# Connectors.net
KiCad netlist of a schematic drawn in Altium Designer
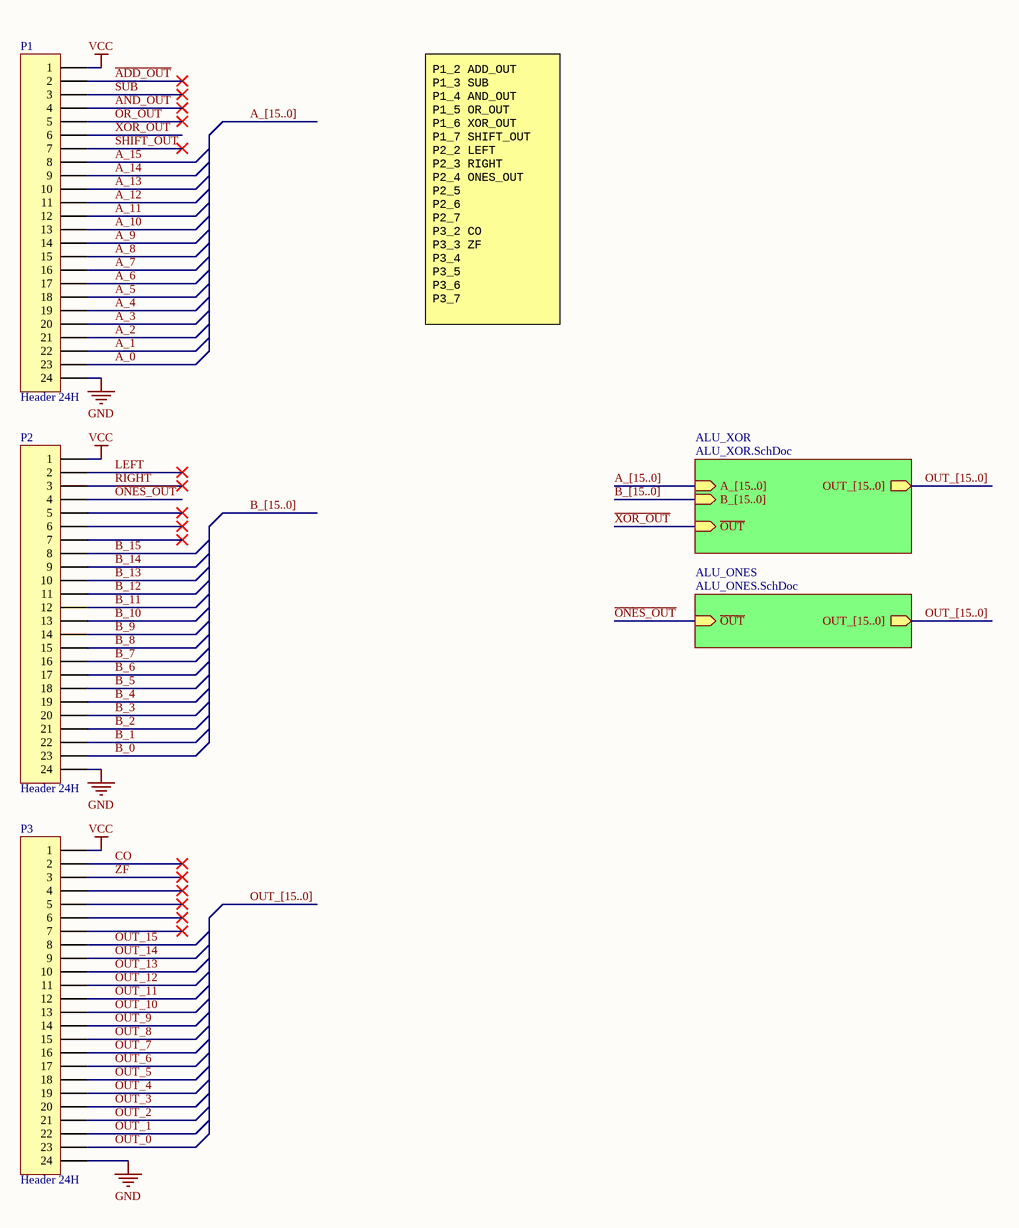
[diagram p0: Connectors.SchDoc]

(export (version "E")
  (design (tool "Eeschema 10.0.6"))
  (components
    (comp (ref "P1")
      (value "Header 24H")
      (footprint "HDR1X24H")
      (description "Header, 24-Pin, Right Angle")
      (fields (field (name "PUBLISHER") "Altium Limited"))
      (libsource (lib "Miscellaneous Connectors") (part "Header 24H"))
    )
    (comp (ref "P2")
      (value "Header 24H")
      (footprint "HDR1X24H")
      (description "Header, 24-Pin, Right Angle")
      (fields (field (name "PUBLISHER") "Altium Limited"))
      (libsource (lib "Miscellaneous Connectors") (part "Header 24H"))
    )
    (comp (ref "P3")
      (value "Header 24H")
      (footprint "HDR1X24H")
      (description "Header, 24-Pin, Right Angle")
      (fields (field (name "PUBLISHER") "Altium Limited"))
      (libsource (lib "Miscellaneous Connectors") (part "Header 24H"))
    )
  )
  (nets
    (net (code "1") (name "/A_0") (class "Default")
      (node (ref "P1") (pin "23") (pinfunction "23_23") (pintype "passive"))
    )
    (net (code "2") (name "/A_1") (class "Default")
      (node (ref "P1") (pin "22") (pinfunction "22_22") (pintype "passive"))
    )
    (net (code "3") (name "/A_2") (class "Default")
      (node (ref "P1") (pin "21") (pinfunction "21_21") (pintype "passive"))
    )
    (net (code "4") (name "/A_3") (class "Default")
      (node (ref "P1") (pin "20") (pinfunction "20_20") (pintype "passive"))
    )
    (net (code "5") (name "/A_4") (class "Default")
      (node (ref "P1") (pin "19") (pinfunction "19_19") (pintype "passive"))
    )
    (net (code "6") (name "/A_5") (class "Default")
      (node (ref "P1") (pin "18") (pinfunction "18_18") (pintype "passive"))
    )
    (net (code "7") (name "/A_6") (class "Default")
      (node (ref "P1") (pin "17") (pinfunction "17_17") (pintype "passive"))
    )
    (net (code "8") (name "/A_7") (class "Default")
      (node (ref "P1") (pin "16") (pinfunction "16_16") (pintype "passive"))
    )
    (net (code "9") (name "/A_8") (class "Default")
      (node (ref "P1") (pin "15") (pinfunction "15_15") (pintype "passive"))
    )
    (net (code "10") (name "/A_9") (class "Default")
      (node (ref "P1") (pin "14") (pinfunction "14_14") (pintype "passive"))
    )
    (net (code "11") (name "/A_10") (class "Default")
      (node (ref "P1") (pin "13") (pinfunction "13_13") (pintype "passive"))
    )
    (net (code "12") (name "/A_11") (class "Default")
      (node (ref "P1") (pin "12") (pinfunction "12_12") (pintype "passive"))
    )
    (net (code "13") (name "/A_12") (class "Default")
      (node (ref "P1") (pin "11") (pinfunction "11_11") (pintype "passive"))
    )
    (net (code "14") (name "/A_13") (class "Default")
      (node (ref "P1") (pin "10") (pinfunction "10_10") (pintype "passive"))
    )
    (net (code "15") (name "/A_14") (class "Default")
      (node (ref "P1") (pin "9") (pinfunction "9_9") (pintype "passive"))
    )
    (net (code "16") (name "/A_15") (class "Default")
      (node (ref "P1") (pin "8") (pinfunction "8_8") (pintype "passive"))
    )
    (net (code "18") (name "/B_0") (class "Default")
      (node (ref "P2") (pin "23") (pinfunction "23_23") (pintype "passive"))
    )
    (net (code "19") (name "/B_1") (class "Default")
      (node (ref "P2") (pin "22") (pinfunction "22_22") (pintype "passive"))
    )
    (net (code "20") (name "/B_2") (class "Default")
      (node (ref "P2") (pin "21") (pinfunction "21_21") (pintype "passive"))
    )
    (net (code "21") (name "/B_3") (class "Default")
      (node (ref "P2") (pin "20") (pinfunction "20_20") (pintype "passive"))
    )
    (net (code "22") (name "/B_4") (class "Default")
      (node (ref "P2") (pin "19") (pinfunction "19_19") (pintype "passive"))
    )
    (net (code "23") (name "/B_5") (class "Default")
      (node (ref "P2") (pin "18") (pinfunction "18_18") (pintype "passive"))
    )
    (net (code "24") (name "/B_6") (class "Default")
      (node (ref "P2") (pin "17") (pinfunction "17_17") (pintype "passive"))
    )
    (net (code "25") (name "/B_7") (class "Default")
      (node (ref "P2") (pin "16") (pinfunction "16_16") (pintype "passive"))
    )
    (net (code "26") (name "/B_8") (class "Default")
      (node (ref "P2") (pin "15") (pinfunction "15_15") (pintype "passive"))
    )
    (net (code "27") (name "/B_9") (class "Default")
      (node (ref "P2") (pin "14") (pinfunction "14_14") (pintype "passive"))
    )
    (net (code "28") (name "/B_10") (class "Default")
      (node (ref "P2") (pin "13") (pinfunction "13_13") (pintype "passive"))
    )
    (net (code "29") (name "/B_11") (class "Default")
      (node (ref "P2") (pin "12") (pinfunction "12_12") (pintype "passive"))
    )
    (net (code "30") (name "/B_12") (class "Default")
      (node (ref "P2") (pin "11") (pinfunction "11_11") (pintype "passive"))
    )
    (net (code "31") (name "/B_13") (class "Default")
      (node (ref "P2") (pin "10") (pinfunction "10_10") (pintype "passive"))
    )
    (net (code "32") (name "/B_14") (class "Default")
      (node (ref "P2") (pin "9") (pinfunction "9_9") (pintype "passive"))
    )
    (net (code "33") (name "/B_15") (class "Default")
      (node (ref "P2") (pin "8") (pinfunction "8_8") (pintype "passive"))
    )
    (net (code "35") (name "/CO") (class "Default")
      (node (ref "P3") (pin "2") (pinfunction "2_2") (pintype "passive+no_connect"))
    )
    (net (code "36") (name "/LEFT") (class "Default")
      (node (ref "P2") (pin "2") (pinfunction "2_2") (pintype "passive+no_connect"))
    )
    (net (code "37") (name "/OUT_0") (class "Default")
      (node (ref "P3") (pin "23") (pinfunction "23_23") (pintype "passive"))
    )
    (net (code "38") (name "/OUT_1") (class "Default")
      (node (ref "P3") (pin "22") (pinfunction "22_22") (pintype "passive"))
    )
    (net (code "39") (name "/OUT_2") (class "Default")
      (node (ref "P3") (pin "21") (pinfunction "21_21") (pintype "passive"))
    )
    (net (code "40") (name "/OUT_3") (class "Default")
      (node (ref "P3") (pin "20") (pinfunction "20_20") (pintype "passive"))
    )
    (net (code "41") (name "/OUT_4") (class "Default")
      (node (ref "P3") (pin "19") (pinfunction "19_19") (pintype "passive"))
    )
    (net (code "42") (name "/OUT_5") (class "Default")
      (node (ref "P3") (pin "18") (pinfunction "18_18") (pintype "passive"))
    )
    (net (code "43") (name "/OUT_6") (class "Default")
      (node (ref "P3") (pin "17") (pinfunction "17_17") (pintype "passive"))
    )
    (net (code "44") (name "/OUT_7") (class "Default")
      (node (ref "P3") (pin "16") (pinfunction "16_16") (pintype "passive"))
    )
    (net (code "45") (name "/OUT_8") (class "Default")
      (node (ref "P3") (pin "15") (pinfunction "15_15") (pintype "passive"))
    )
    (net (code "46") (name "/OUT_9") (class "Default")
      (node (ref "P3") (pin "14") (pinfunction "14_14") (pintype "passive"))
    )
    (net (code "47") (name "/OUT_10") (class "Default")
      (node (ref "P3") (pin "13") (pinfunction "13_13") (pintype "passive"))
    )
    (net (code "48") (name "/OUT_11") (class "Default")
      (node (ref "P3") (pin "12") (pinfunction "12_12") (pintype "passive"))
    )
    (net (code "49") (name "/OUT_12") (class "Default")
      (node (ref "P3") (pin "11") (pinfunction "11_11") (pintype "passive"))
    )
    (net (code "50") (name "/OUT_13") (class "Default")
      (node (ref "P3") (pin "10") (pinfunction "10_10") (pintype "passive"))
    )
    (net (code "51") (name "/OUT_14") (class "Default")
      (node (ref "P3") (pin "9") (pinfunction "9_9") (pintype "passive"))
    )
    (net (code "52") (name "/OUT_15") (class "Default")
      (node (ref "P3") (pin "8") (pinfunction "8_8") (pintype "passive"))
    )
    (net (code "54") (name "/RIGHT") (class "Default")
      (node (ref "P2") (pin "3") (pinfunction "3_3") (pintype "passive+no_connect"))
    )
    (net (code "55") (name "/SUB") (class "Default")
      (node (ref "P1") (pin "3") (pinfunction "3_3") (pintype "passive+no_connect"))
    )
    (net (code "56") (name "/~{ADD_OUT}") (class "Default")
      (node (ref "P1") (pin "2") (pinfunction "2_2") (pintype "passive+no_connect"))
    )
    (net (code "57") (name "/~{AND_OUT}") (class "Default")
      (node (ref "P1") (pin "4") (pinfunction "4_4") (pintype "passive+no_connect"))
    )
    (net (code "58") (name "/~{ONES_OUT}") (class "Default")
      (node (ref "P2") (pin "4") (pinfunction "4_4") (pintype "passive"))
    )
    (net (code "59") (name "/~{OR_OUT}") (class "Default")
      (node (ref "P1") (pin "5") (pinfunction "5_5") (pintype "passive+no_connect"))
    )
    (net (code "60") (name "/~{SHIFT_OUT}") (class "Default")
      (node (ref "P1") (pin "7") (pinfunction "7_7") (pintype "passive+no_connect"))
    )
    (net (code "61") (name "/~{XOR_OUT}") (class "Default")
      (node (ref "P1") (pin "6") (pinfunction "6_6") (pintype "passive"))
    )
    (net (code "62") (name "/~{ZF}") (class "Default")
      (node (ref "P3") (pin "3") (pinfunction "3_3") (pintype "passive+no_connect"))
    )
    (net (code "63") (name "GND") (class "Default")
      (node (ref "P1") (pin "24") (pinfunction "24_24") (pintype "passive"))
      (node (ref "P2") (pin "24") (pinfunction "24_24") (pintype "passive"))
      (node (ref "P3") (pin "24") (pinfunction "24_24") (pintype "passive"))
    )
    (net (code "64") (name "VCC") (class "Default")
      (node (ref "P1") (pin "1") (pinfunction "1_1") (pintype "passive"))
      (node (ref "P2") (pin "1") (pinfunction "1_1") (pintype "passive"))
      (node (ref "P3") (pin "1") (pinfunction "1_1") (pintype "passive"))
    )
    (net (code "65") (name "unconnected-(P2-Pad5)") (class "Default")
      (node (ref "P2") (pin "5") (pinfunction "5_5") (pintype "passive+no_connect"))
    )
    (net (code "66") (name "unconnected-(P2-Pad6)") (class "Default")
      (node (ref "P2") (pin "6") (pinfunction "6_6") (pintype "passive+no_connect"))
    )
    (net (code "67") (name "unconnected-(P2-Pad7)") (class "Default")
      (node (ref "P2") (pin "7") (pinfunction "7_7") (pintype "passive+no_connect"))
    )
    (net (code "68") (name "unconnected-(P3-Pad4)") (class "Default")
      (node (ref "P3") (pin "4") (pinfunction "4_4") (pintype "passive+no_connect"))
    )
    (net (code "69") (name "unconnected-(P3-Pad5)") (class "Default")
      (node (ref "P3") (pin "5") (pinfunction "5_5") (pintype "passive+no_connect"))
    )
    (net (code "70") (name "unconnected-(P3-Pad6)") (class "Default")
      (node (ref "P3") (pin "6") (pinfunction "6_6") (pintype "passive+no_connect"))
    )
    (net (code "71") (name "unconnected-(P3-Pad7)") (class "Default")
      (node (ref "P3") (pin "7") (pinfunction "7_7") (pintype "passive+no_connect"))
    )
  )
)
